# VEML6070-Breakout_v11.net
KiCad netlist of a schematic drawn in EAGLE
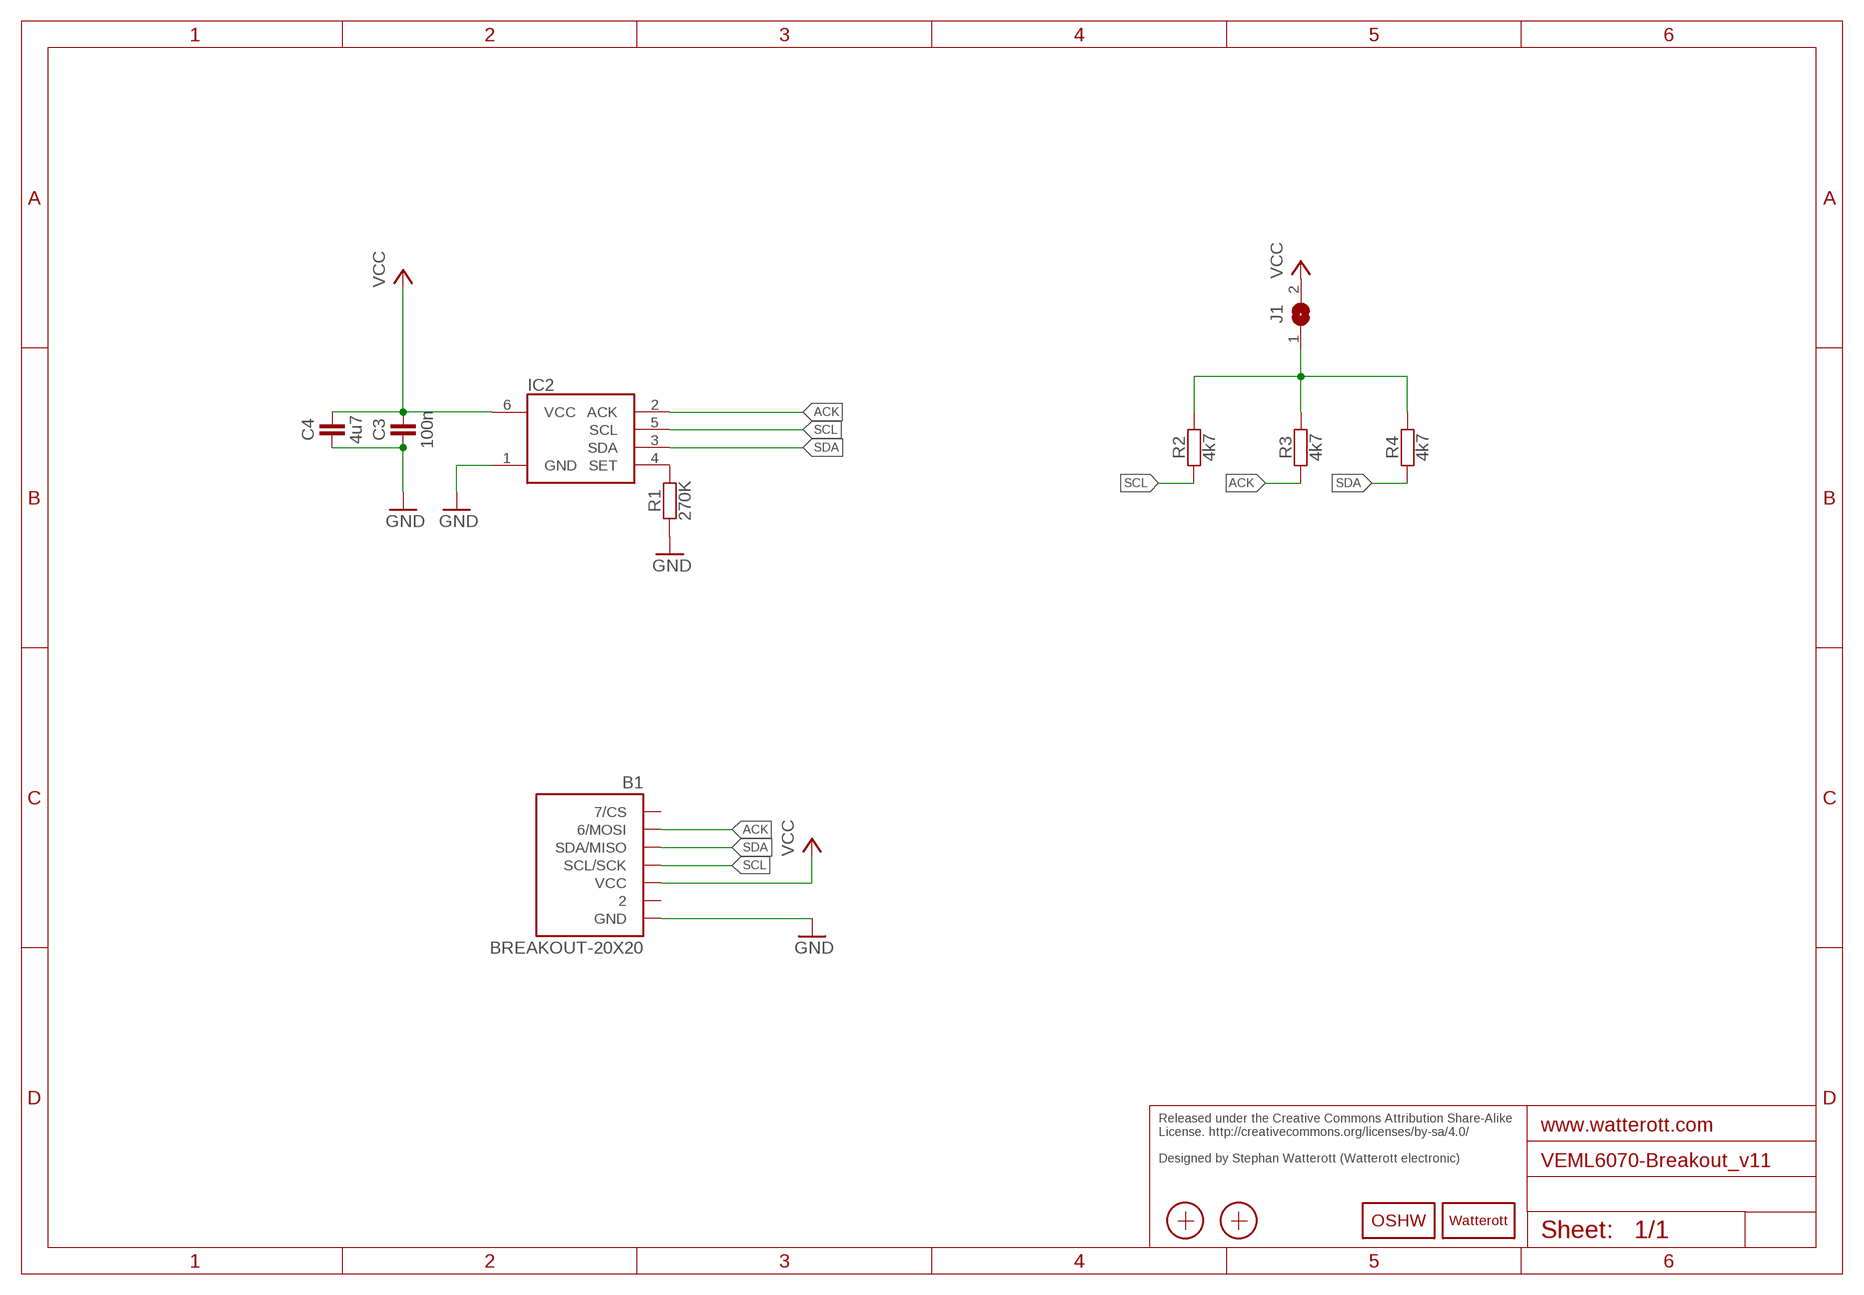
[diagram p0: schematic, sheet 1]

(export (version "E")
  (design (tool "Eeschema 10.0.6"))
  (components
    (comp (ref "B1")
      (value "BREAKOUT-20X20")
      (footprint "eagle-import:BREAKOUT-20X20")
      (libsource (lib "eagle-import") (part "BREAKOUT-20X20"))
    )
    (comp (ref "C3")
      (value "100n")
      (footprint "eagle-import:R0402")
      (libsource (lib "eagle-import") (part "CAPACITOR-C0402"))
    )
    (comp (ref "C4")
      (value "4u7")
      (footprint "eagle-import:R0402")
      (libsource (lib "eagle-import") (part "CAPACITOR-C0402"))
    )
    (comp (ref "IC2")
      (value "VEML6070")
      (footprint "eagle-import:OPLGA")
      (libsource (lib "eagle-import") (part "VEML6070"))
    )
    (comp (ref "J1")
      (value "JUMPER2-0603-NC")
      (footprint "eagle-import:JUMPER2-0603_NC")
      (libsource (lib "eagle-import") (part "JUMPER2-0603-NC"))
    )
    (comp (ref "LOGO1")
      (value "LOGO-S_PLACE_M")
      (footprint "eagle-import:SPARK_TPLACE_M")
      (libsource (lib "eagle-import") (part "LOGO-S_PLACE_M"))
    )
    (comp (ref "LOGO2")
      (value "OSHW_LOGOX0070")
      (footprint "eagle-import:OSHW_6X70")
      (libsource (lib "eagle-import") (part "OSHW_LOGOX0070"))
    )
    (comp (ref "R1")
      (value "270K")
      (footprint "eagle-import:R0402")
      (libsource (lib "eagle-import") (part "RESISTOR-R0402"))
    )
    (comp (ref "R2")
      (value "4k7")
      (footprint "eagle-import:R0402")
      (libsource (lib "eagle-import") (part "RESISTOR-R0402"))
    )
    (comp (ref "R3")
      (value "4k7")
      (footprint "eagle-import:R0402")
      (libsource (lib "eagle-import") (part "RESISTOR-R0402"))
    )
    (comp (ref "R4")
      (value "4k7")
      (footprint "eagle-import:R0402")
      (libsource (lib "eagle-import") (part "RESISTOR-R0402"))
    )
    (comp (ref "X1")
      (value "PASSER-07")
      (footprint "eagle-import:PASSER_07MM")
      (libsource (lib "eagle-import") (part "PASSER-07"))
    )
    (comp (ref "X2")
      (value "PASSER-07")
      (footprint "eagle-import:PASSER_07MM")
      (libsource (lib "eagle-import") (part "PASSER-07"))
    )
  )
  (nets
    (net (code "1") (name "ACK") (class "Default")
      (node (ref "B1") (pin "MOSI") (pinfunction "6/MOSI_MOSI") (pintype "bidirectional"))
      (node (ref "IC2") (pin "2") (pinfunction "ACK_2") (pintype "output"))
      (node (ref "R3") (pin "1") (pinfunction "1_1") (pintype "passive"))
    )
    (net (code "2") (name "GND") (class "Default")
      (node (ref "B1") (pin "GND") (pinfunction "GND_GND") (pintype "power_in"))
      (node (ref "C3") (pin "1") (pinfunction "1_1") (pintype "passive"))
      (node (ref "C4") (pin "1") (pinfunction "1_1") (pintype "passive"))
      (node (ref "IC2") (pin "1") (pinfunction "GND_1") (pintype "power_in"))
      (node (ref "R1") (pin "1") (pinfunction "1_1") (pintype "passive"))
    )
    (net (code "3") (name "Net-(IC2-SET)") (class "Default")
      (node (ref "IC2") (pin "4") (pinfunction "SET_4") (pintype "bidirectional"))
      (node (ref "R1") (pin "2") (pinfunction "2_2") (pintype "passive"))
    )
    (net (code "4") (name "Net-(J1-Pad1)") (class "Default")
      (node (ref "J1") (pin "1") (pinfunction "1_1") (pintype "passive"))
      (node (ref "R2") (pin "2") (pinfunction "2_2") (pintype "passive"))
      (node (ref "R3") (pin "2") (pinfunction "2_2") (pintype "passive"))
      (node (ref "R4") (pin "2") (pinfunction "2_2") (pintype "passive"))
    )
    (net (code "5") (name "SCL") (class "Default")
      (node (ref "B1") (pin "SCL/SCK") (pinfunction "SCL/SCK_SCL/SCK") (pintype "bidirectional"))
      (node (ref "IC2") (pin "5") (pinfunction "SCL_5") (pintype "input"))
      (node (ref "R2") (pin "1") (pinfunction "1_1") (pintype "passive"))
    )
    (net (code "6") (name "SDA") (class "Default")
      (node (ref "B1") (pin "SDA/MISO") (pinfunction "SDA/MISO_SDA/MISO") (pintype "bidirectional"))
      (node (ref "IC2") (pin "3") (pinfunction "SDA_3") (pintype "bidirectional"))
      (node (ref "R4") (pin "1") (pinfunction "1_1") (pintype "passive"))
    )
    (net (code "7") (name "VCC") (class "Default")
      (node (ref "B1") (pin "VCC") (pinfunction "VCC_VCC") (pintype "power_in"))
      (node (ref "C3") (pin "2") (pinfunction "2_2") (pintype "passive"))
      (node (ref "C4") (pin "2") (pinfunction "2_2") (pintype "passive"))
      (node (ref "IC2") (pin "6") (pinfunction "VCC_6") (pintype "power_in"))
      (node (ref "J1") (pin "2") (pinfunction "2_2") (pintype "passive"))
    )
    (net (code "8") (name "unconnected-(B1-7{slash}CS-PadCS)") (class "Default")
      (node (ref "B1") (pin "CS") (pinfunction "7/CS_CS") (pintype "bidirectional"))
    )
    (net (code "9") (name "unconnected-(B1-Pad2)") (class "Default")
      (node (ref "B1") (pin "2") (pinfunction "2_2") (pintype "bidirectional"))
    )
  )
)
